# PowerRailBoard.net
KiCad netlist of a schematic drawn in EAGLE
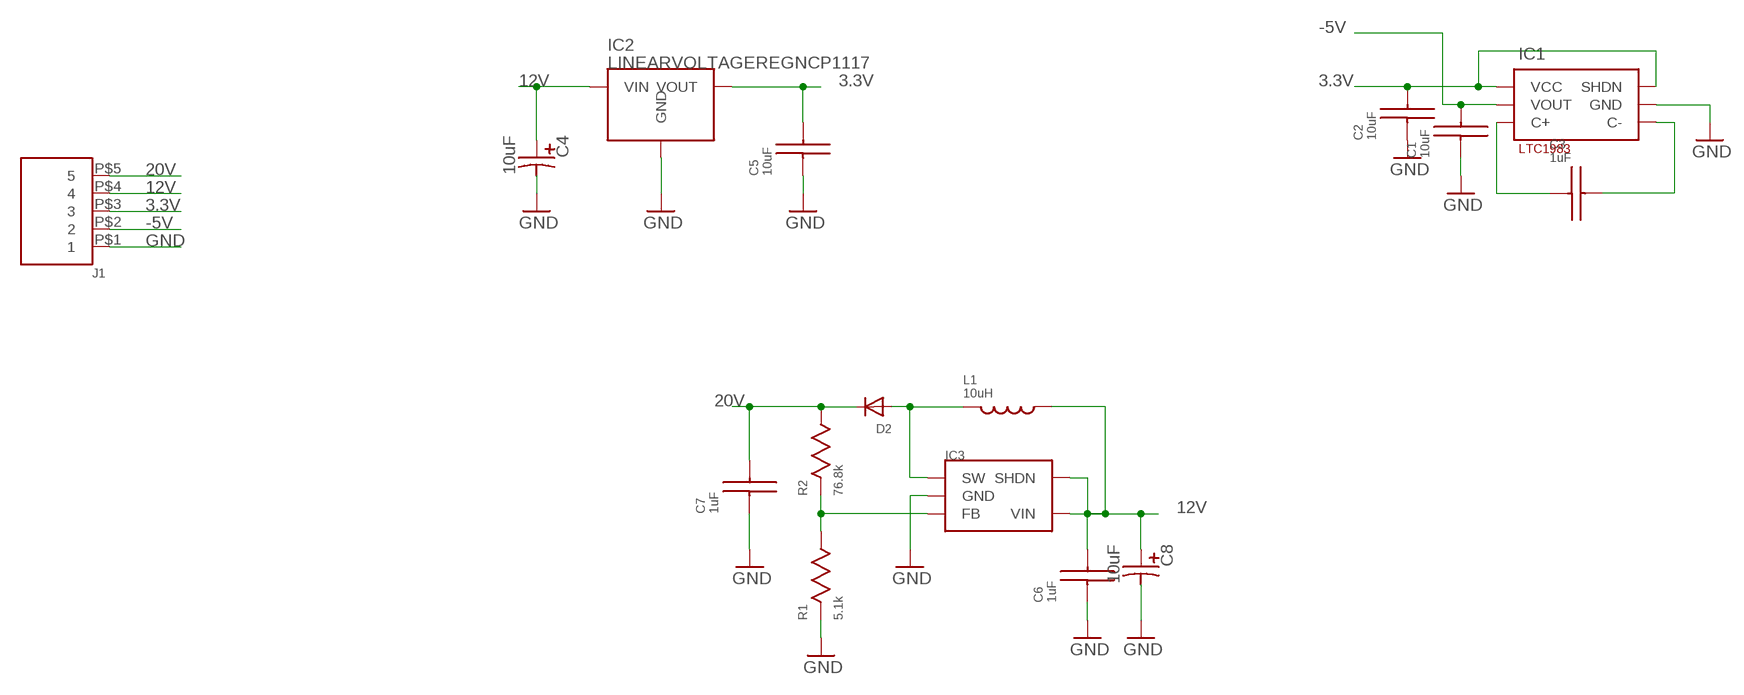
[diagram p0: schematic, sheet 1]

(export (version "E")
  (design (tool "Eeschema 10.0.6"))
  (components
    (comp (ref "C1")
      (value "10uF")
      (footprint "eagle-import:0805_(2012_METRIC)")
      (libsource (lib "eagle-import") (part "CHIP_CAP0805"))
    )
    (comp (ref "C2")
      (value "10uF")
      (footprint "eagle-import:0805_(2012_METRIC)")
      (libsource (lib "eagle-import") (part "CHIP_CAP0805"))
    )
    (comp (ref "C3")
      (value "1uF")
      (footprint "eagle-import:0805_(2012_METRIC)")
      (libsource (lib "eagle-import") (part "CHIP_CAP0805"))
    )
    (comp (ref "C4")
      (value "10uF")
      (footprint "eagle-import:CAP_SSER_5MMX5MM")
      (libsource (lib "eagle-import") (part "CHIP_CAP_POLB"))
    )
    (comp (ref "C5")
      (value "10uF")
      (footprint "eagle-import:0805_(2012_METRIC)")
      (libsource (lib "eagle-import") (part "CHIP_CAP0805"))
    )
    (comp (ref "C6")
      (value "1uF")
      (footprint "eagle-import:0805_(2012_METRIC)")
      (libsource (lib "eagle-import") (part "CHIP_CAP0805"))
    )
    (comp (ref "C7")
      (value "1uF")
      (footprint "eagle-import:0805_(2012_METRIC)")
      (libsource (lib "eagle-import") (part "CHIP_CAP0805"))
    )
    (comp (ref "C8")
      (value "10uF")
      (footprint "eagle-import:CAP_SSER_5MMX5MM")
      (libsource (lib "eagle-import") (part "CHIP_CAP_POLB"))
    )
    (comp (ref "D2")
      (value "DIODESOD-123")
      (footprint "eagle-import:SOD-123")
      (libsource (lib "eagle-import") (part "DIODESOD-123"))
    )
    (comp (ref "IC1")
      (value "LTC1983")
      (footprint "eagle-import:TSOT23-6")
      (libsource (lib "eagle-import") (part "LTC1983"))
    )
    (comp (ref "IC2")
      (value "LINEARVOLTAGEREGNCP1117")
      (footprint "eagle-import:DPAK")
      (libsource (lib "eagle-import") (part "LINEARVOLTAGEREGNCP1117"))
    )
    (comp (ref "IC3")
      (value "AP301")
      (footprint "eagle-import:SOT-23")
      (libsource (lib "eagle-import") (part "AP301"))
    )
    (comp (ref "J1")
      (value "CONNECTOR_5PIN")
      (footprint "eagle-import:5PIN_.1'")
      (libsource (lib "eagle-import") (part "CONNECTOR_5PIN"))
    )
    (comp (ref "L1")
      (value "10uH")
      (footprint "eagle-import:0805_(2012_METRIC)")
      (libsource (lib "eagle-import") (part "CHIP_IND"))
    )
    (comp (ref "R1")
      (value "5.1k")
      (footprint "eagle-import:0805_(2012_METRIC)")
      (libsource (lib "eagle-import") (part "CHIP_RES0805"))
    )
    (comp (ref "R2")
      (value "76.8k")
      (footprint "eagle-import:0805_(2012_METRIC)")
      (libsource (lib "eagle-import") (part "CHIP_RES0805"))
    )
  )
  (nets
    (net (code "1") (name "/-5V") (class "Default")
      (node (ref "C1") (pin "P$1") (pinfunction "P$2_P$1") (pintype "bidirectional"))
      (node (ref "IC1") (pin "2") (pinfunction "VOUT_2") (pintype "bidirectional"))
      (node (ref "J1") (pin "P$2") (pinfunction "2_P$2") (pintype "bidirectional"))
    )
    (net (code "2") (name "/3.3V") (class "Default")
      (node (ref "C2") (pin "P$1") (pinfunction "P$2_P$1") (pintype "bidirectional"))
      (node (ref "C5") (pin "P$1") (pinfunction "P$2_P$1") (pintype "bidirectional"))
      (node (ref "IC1") (pin "1") (pinfunction "VCC_1") (pintype "bidirectional"))
      (node (ref "IC1") (pin "6") (pinfunction "SHDN_6") (pintype "bidirectional"))
      (node (ref "IC2") (pin "2") (pinfunction "VOUT_2") (pintype "bidirectional"))
      (node (ref "J1") (pin "P$3") (pinfunction "3_P$3") (pintype "bidirectional"))
    )
    (net (code "3") (name "/12V") (class "Default")
      (node (ref "C4") (pin "P") (pinfunction "POSITIVE_P") (pintype "bidirectional"))
      (node (ref "C6") (pin "P$1") (pinfunction "P$2_P$1") (pintype "bidirectional"))
      (node (ref "C8") (pin "P") (pinfunction "POSITIVE_P") (pintype "bidirectional"))
      (node (ref "IC2") (pin "3") (pinfunction "VIN_3") (pintype "bidirectional"))
      (node (ref "IC3") (pin "4") (pinfunction "SHDN_4") (pintype "bidirectional"))
      (node (ref "IC3") (pin "5") (pinfunction "VIN_5") (pintype "bidirectional"))
      (node (ref "J1") (pin "P$4") (pinfunction "4_P$4") (pintype "bidirectional"))
      (node (ref "L1") (pin "P$2") (pinfunction "P$2_P$2") (pintype "bidirectional"))
    )
    (net (code "4") (name "/20V") (class "Default")
      (node (ref "C7") (pin "P$1") (pinfunction "P$2_P$1") (pintype "bidirectional"))
      (node (ref "D2") (pin "C") (pinfunction "C_C") (pintype "passive"))
      (node (ref "J1") (pin "P$5") (pinfunction "5_P$5") (pintype "bidirectional"))
      (node (ref "R2") (pin "P$1") (pinfunction "P$2_P$1") (pintype "bidirectional"))
    )
    (net (code "5") (name "GND") (class "Default")
      (node (ref "C1") (pin "P$2") (pinfunction "P$1_P$2") (pintype "bidirectional"))
      (node (ref "C2") (pin "P$2") (pinfunction "P$1_P$2") (pintype "bidirectional"))
      (node (ref "C4") (pin "N") (pinfunction "NEGATIVE_N") (pintype "bidirectional"))
      (node (ref "C5") (pin "P$2") (pinfunction "P$1_P$2") (pintype "bidirectional"))
      (node (ref "C6") (pin "P$2") (pinfunction "P$1_P$2") (pintype "bidirectional"))
      (node (ref "C7") (pin "P$2") (pinfunction "P$1_P$2") (pintype "bidirectional"))
      (node (ref "C8") (pin "N") (pinfunction "NEGATIVE_N") (pintype "bidirectional"))
      (node (ref "IC1") (pin "5") (pinfunction "GND_5") (pintype "bidirectional"))
      (node (ref "IC2") (pin "1") (pinfunction "GND_1") (pintype "bidirectional"))
      (node (ref "IC3") (pin "2") (pinfunction "GND_2") (pintype "bidirectional"))
      (node (ref "J1") (pin "P$1") (pinfunction "1_P$1") (pintype "bidirectional"))
      (node (ref "R1") (pin "P$2") (pinfunction "P$1_P$2") (pintype "bidirectional"))
    )
    (net (code "6") (name "Net-(C3-P$1)") (class "Default")
      (node (ref "C3") (pin "P$2") (pinfunction "P$1_P$2") (pintype "bidirectional"))
      (node (ref "IC1") (pin "3") (pinfunction "C+_3") (pintype "bidirectional"))
    )
    (net (code "7") (name "Net-(C3-P$2)") (class "Default")
      (node (ref "C3") (pin "P$1") (pinfunction "P$2_P$1") (pintype "bidirectional"))
      (node (ref "IC1") (pin "4") (pinfunction "C-_4") (pintype "bidirectional"))
    )
    (net (code "8") (name "Net-(IC3-FB)") (class "Default")
      (node (ref "IC3") (pin "3") (pinfunction "FB_3") (pintype "bidirectional"))
      (node (ref "R1") (pin "P$1") (pinfunction "P$2_P$1") (pintype "bidirectional"))
      (node (ref "R2") (pin "P$2") (pinfunction "P$1_P$2") (pintype "bidirectional"))
    )
    (net (code "9") (name "Net-(IC3-SW)") (class "Default")
      (node (ref "D2") (pin "A") (pinfunction "A_A") (pintype "passive"))
      (node (ref "IC3") (pin "1") (pinfunction "SW_1") (pintype "bidirectional"))
      (node (ref "L1") (pin "P$1") (pinfunction "P$1_P$1") (pintype "bidirectional"))
    )
  )
)
